# xor.net
KiCad netlist of a schematic drawn in EAGLE
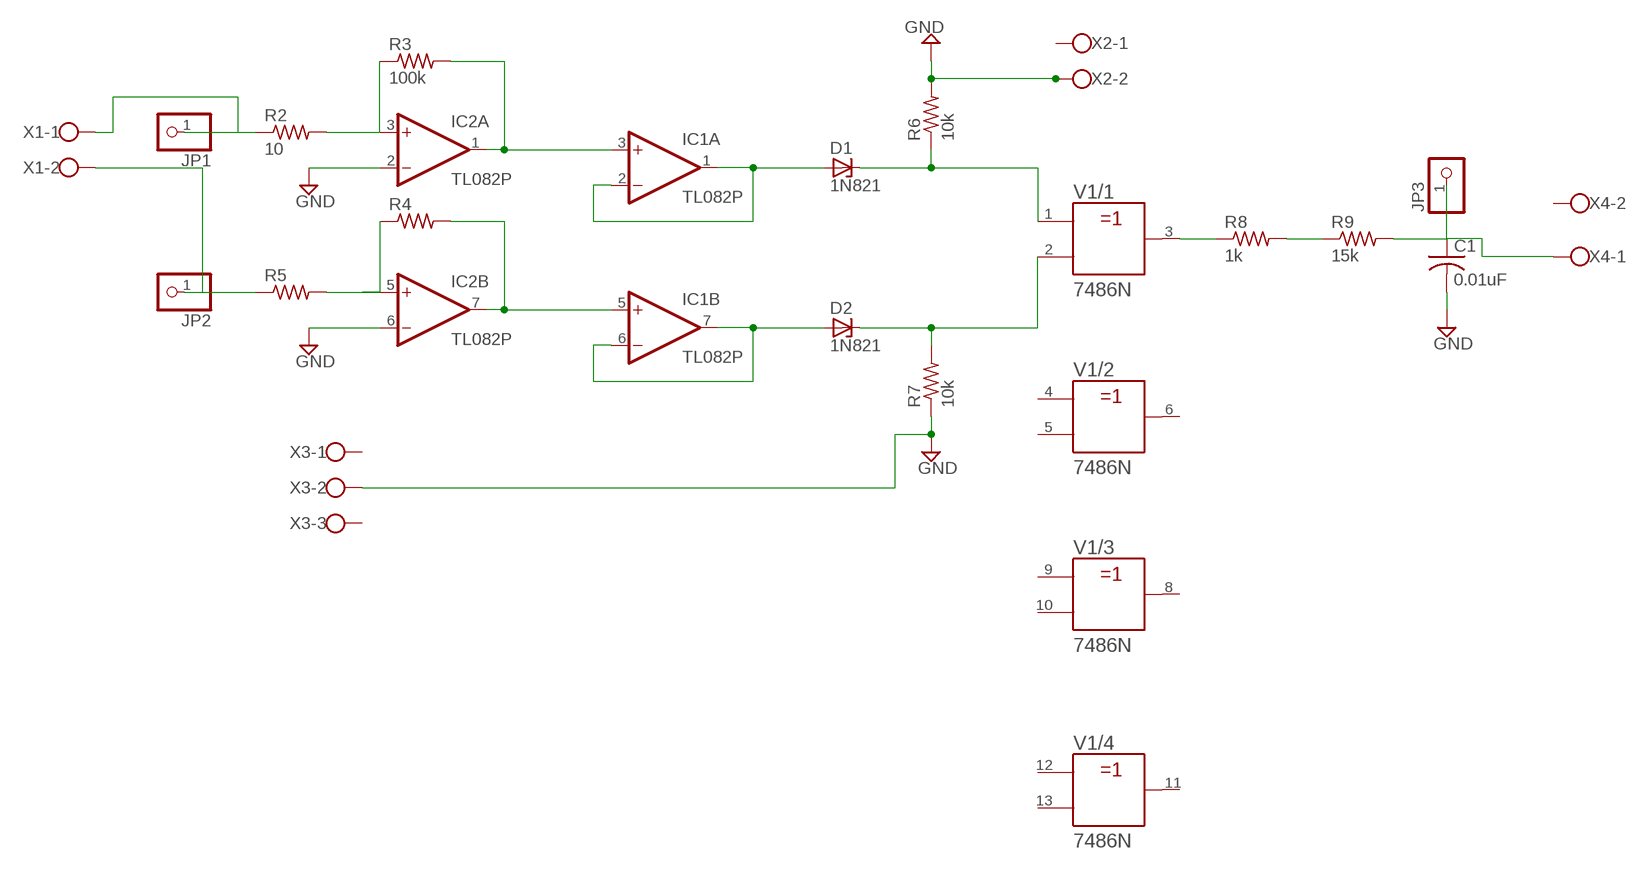
[diagram p0: schematic, sheet 1]

(export (version "E")
  (design (tool "Eeschema 10.0.6"))
  (components
    (comp (ref "C1")
      (value "0.01uF")
      (footprint "eagle-import:C050-045X075")
      (libsource (lib "eagle-import") (part "C-US050-045X075"))
    )
    (comp (ref "D1")
      (value "1N821")
      (footprint "eagle-import:DO35Z10")
      (libsource (lib "eagle-import") (part "1N821"))
    )
    (comp (ref "D2")
      (value "1N821")
      (footprint "eagle-import:DO35Z10")
      (libsource (lib "eagle-import") (part "1N821"))
    )
    (comp (ref "IC1")
      (value "TL082P")
      (footprint "eagle-import:DIL08")
      (libsource (lib "eagle-import") (part "TL082P"))
    )
    (comp (ref "IC2")
      (value "TL082P")
      (footprint "eagle-import:DIL08")
      (libsource (lib "eagle-import") (part "TL082P"))
    )
    (comp (ref "JP1")
      (value "PINHD-1X1CB")
      (footprint "eagle-import:1X01-CLEANBIG")
      (libsource (lib "eagle-import") (part "PINHD-1X1CB"))
    )
    (comp (ref "JP2")
      (value "PINHD-1X1CB")
      (footprint "eagle-import:1X01-CLEANBIG")
      (libsource (lib "eagle-import") (part "PINHD-1X1CB"))
    )
    (comp (ref "JP3")
      (value "PINHD-1X1CB")
      (footprint "eagle-import:1X01-CLEANBIG")
      (libsource (lib "eagle-import") (part "PINHD-1X1CB"))
    )
    (comp (ref "R2")
      (value "10")
      (footprint "eagle-import:0309_10")
      (libsource (lib "eagle-import") (part "R-US_0309/10"))
    )
    (comp (ref "R3")
      (value "100k")
      (footprint "eagle-import:0309_10")
      (libsource (lib "eagle-import") (part "R-US_0309/10"))
    )
    (comp (ref "R4")
      (value "R-US_0309/10")
      (footprint "eagle-import:0309_10")
      (libsource (lib "eagle-import") (part "R-US_0309/10"))
    )
    (comp (ref "R5")
      (value "R-US_0309/10")
      (footprint "eagle-import:0309_10")
      (libsource (lib "eagle-import") (part "R-US_0309/10"))
    )
    (comp (ref "R6")
      (value "10k")
      (footprint "eagle-import:0309_10")
      (libsource (lib "eagle-import") (part "R-US_0309/10"))
    )
    (comp (ref "R7")
      (value "10k")
      (footprint "eagle-import:0309_10")
      (libsource (lib "eagle-import") (part "R-US_0309/10"))
    )
    (comp (ref "R8")
      (value "1k")
      (footprint "eagle-import:0309_10")
      (libsource (lib "eagle-import") (part "R-US_0309/10"))
    )
    (comp (ref "R9")
      (value "15k")
      (footprint "eagle-import:0309_10")
      (libsource (lib "eagle-import") (part "R-US_0309/10"))
    )
    (comp (ref "V1")
      (value "7486N")
      (footprint "eagle-import:DIL14")
      (libsource (lib "eagle-import") (part "7486N"))
    )
    (comp (ref "X1")
      (value "W237-102")
      (footprint "eagle-import:W237-102")
      (fields (field (name "MPN") "237-102"))
      (libsource (lib "eagle-import") (part "W237-102"))
    )
    (comp (ref "X2")
      (value "W237-102")
      (footprint "eagle-import:W237-102")
      (fields (field (name "MPN") "237-102"))
      (libsource (lib "eagle-import") (part "W237-102"))
    )
    (comp (ref "X3")
      (value "W237-103")
      (footprint "eagle-import:W237-103")
      (fields (field (name "MPN") "237-103"))
      (libsource (lib "eagle-import") (part "W237-103"))
    )
    (comp (ref "X4")
      (value "W237-102")
      (footprint "eagle-import:W237-102")
      (fields (field (name "MPN") "237-102"))
      (libsource (lib "eagle-import") (part "W237-102"))
    )
  )
  (nets
    (net (code "1") (name "GND") (class "Default")
      (node (ref "C1") (pin "2") (pinfunction "2_2") (pintype "passive"))
      (node (ref "IC2") (pin "2") (pinfunction "-IN_2") (pintype "input"))
      (node (ref "IC2") (pin "6") (pinfunction "-IN_6") (pintype "input"))
      (node (ref "R6") (pin "2") (pinfunction "2_2") (pintype "passive"))
      (node (ref "R7") (pin "1") (pinfunction "1_1") (pintype "passive"))
      (node (ref "X2") (pin "2") (pinfunction "KL_2") (pintype "passive"))
      (node (ref "X3") (pin "2") (pinfunction "KL_2") (pintype "passive"))
    )
    (net (code "2") (name "Net-(IC1A-+IN)") (class "Default")
      (node (ref "IC1") (pin "3") (pinfunction "+IN_3") (pintype "input"))
      (node (ref "IC2") (pin "1") (pinfunction "OUT_1") (pintype "output"))
      (node (ref "R3") (pin "2") (pinfunction "2_2") (pintype "passive"))
    )
    (net (code "3") (name "Net-(IC1A--IN)") (class "Default")
      (node (ref "D1") (pin "A") (pinfunction "A_A") (pintype "passive"))
      (node (ref "IC1") (pin "1") (pinfunction "OUT_1") (pintype "output"))
      (node (ref "IC1") (pin "2") (pinfunction "-IN_2") (pintype "input"))
    )
    (net (code "4") (name "Net-(IC1B-+IN)") (class "Default")
      (node (ref "IC1") (pin "5") (pinfunction "+IN_5") (pintype "input"))
      (node (ref "IC2") (pin "7") (pinfunction "OUT_7") (pintype "output"))
      (node (ref "R4") (pin "2") (pinfunction "2_2") (pintype "passive"))
    )
    (net (code "5") (name "Net-(IC1B--IN)") (class "Default")
      (node (ref "D2") (pin "A") (pinfunction "A_A") (pintype "passive"))
      (node (ref "IC1") (pin "6") (pinfunction "-IN_6") (pintype "input"))
      (node (ref "IC1") (pin "7") (pinfunction "OUT_7") (pintype "output"))
    )
    (net (code "6") (name "Net-(IC2A-+IN)") (class "Default")
      (node (ref "IC2") (pin "3") (pinfunction "+IN_3") (pintype "input"))
      (node (ref "R2") (pin "2") (pinfunction "2_2") (pintype "passive"))
      (node (ref "R3") (pin "1") (pinfunction "1_1") (pintype "passive"))
    )
    (net (code "7") (name "Net-(IC2B-+IN)") (class "Default")
      (node (ref "IC2") (pin "5") (pinfunction "+IN_5") (pintype "input"))
      (node (ref "R4") (pin "1") (pinfunction "1_1") (pintype "passive"))
      (node (ref "R5") (pin "2") (pinfunction "2_2") (pintype "passive"))
    )
    (net (code "8") (name "Net-(R8-Pad2)") (class "Default")
      (node (ref "R8") (pin "2") (pinfunction "2_2") (pintype "passive"))
      (node (ref "R9") (pin "1") (pinfunction "1_1") (pintype "passive"))
    )
    (net (code "9") (name "Net-(V1C-A)") (class "Default")
      (node (ref "D1") (pin "C") (pinfunction "C_C") (pintype "passive"))
      (node (ref "R6") (pin "1") (pinfunction "1_1") (pintype "passive"))
      (node (ref "V1") (pin "1") (pinfunction "A_1") (pintype "input"))
    )
    (net (code "10") (name "Net-(V1C-B)") (class "Default")
      (node (ref "D2") (pin "C") (pinfunction "C_C") (pintype "passive"))
      (node (ref "R7") (pin "2") (pinfunction "2_2") (pintype "passive"))
      (node (ref "V1") (pin "2") (pinfunction "B_2") (pintype "input"))
    )
    (net (code "11") (name "Net-(V1C-Y)") (class "Default")
      (node (ref "R8") (pin "1") (pinfunction "1_1") (pintype "passive"))
      (node (ref "V1") (pin "3") (pinfunction "Y_3") (pintype "output"))
    )
    (net (code "12") (name "Net-(X1A-KL)") (class "Default")
      (node (ref "JP1") (pin "1") (pinfunction "1_1") (pintype "passive"))
      (node (ref "R2") (pin "1") (pinfunction "1_1") (pintype "passive"))
      (node (ref "X1") (pin "1") (pinfunction "KL_1") (pintype "passive"))
    )
    (net (code "13") (name "Net-(X1B-KL)") (class "Default")
      (node (ref "JP2") (pin "1") (pinfunction "1_1") (pintype "passive"))
      (node (ref "R5") (pin "1") (pinfunction "1_1") (pintype "passive"))
      (node (ref "X1") (pin "2") (pinfunction "KL_2") (pintype "passive"))
    )
    (net (code "14") (name "Net-(X4A-KL)") (class "Default")
      (node (ref "C1") (pin "1") (pinfunction "1_1") (pintype "passive"))
      (node (ref "JP3") (pin "1") (pinfunction "1_1") (pintype "passive"))
      (node (ref "R9") (pin "2") (pinfunction "2_2") (pintype "passive"))
      (node (ref "X4") (pin "1") (pinfunction "KL_1") (pintype "passive"))
    )
    (net (code "15") (name "unconnected-(V1D-A-Pad4)") (class "Default")
      (node (ref "V1") (pin "4") (pinfunction "A_4") (pintype "input"))
    )
    (net (code "16") (name "unconnected-(V1D-B-Pad5)") (class "Default")
      (node (ref "V1") (pin "5") (pinfunction "B_5") (pintype "input"))
    )
    (net (code "17") (name "unconnected-(V1D-Y-Pad6)") (class "Default")
      (node (ref "V1") (pin "6") (pinfunction "Y_6") (pintype "output"))
    )
    (net (code "18") (name "unconnected-(V1E-A-Pad9)") (class "Default")
      (node (ref "V1") (pin "9") (pinfunction "A_9") (pintype "input"))
    )
    (net (code "19") (name "unconnected-(V1E-B-Pad10)") (class "Default")
      (node (ref "V1") (pin "10") (pinfunction "B_10") (pintype "input"))
    )
    (net (code "20") (name "unconnected-(V1E-Y-Pad8)") (class "Default")
      (node (ref "V1") (pin "8") (pinfunction "Y_8") (pintype "output"))
    )
    (net (code "21") (name "unconnected-(V1F-A-Pad12)") (class "Default")
      (node (ref "V1") (pin "12") (pinfunction "A_12") (pintype "input"))
    )
    (net (code "22") (name "unconnected-(V1F-B-Pad13)") (class "Default")
      (node (ref "V1") (pin "13") (pinfunction "B_13") (pintype "input"))
    )
    (net (code "23") (name "unconnected-(V1F-Y-Pad11)") (class "Default")
      (node (ref "V1") (pin "11") (pinfunction "Y_11") (pintype "output"))
    )
    (net (code "24") (name "unconnected-(X2A-KL-Pad1)") (class "Default")
      (node (ref "X2") (pin "1") (pinfunction "KL_1") (pintype "passive"))
    )
    (net (code "25") (name "unconnected-(X3A-KL-Pad1)") (class "Default")
      (node (ref "X3") (pin "1") (pinfunction "KL_1") (pintype "passive"))
    )
    (net (code "26") (name "unconnected-(X3C-KL-Pad3)") (class "Default")
      (node (ref "X3") (pin "3") (pinfunction "KL_3") (pintype "passive"))
    )
    (net (code "27") (name "unconnected-(X4B-KL-Pad2)") (class "Default")
      (node (ref "X4") (pin "2") (pinfunction "KL_2") (pintype "passive"))
    )
  )
)
